# final_schematic.net
KiCad netlist of a schematic drawn in EAGLE
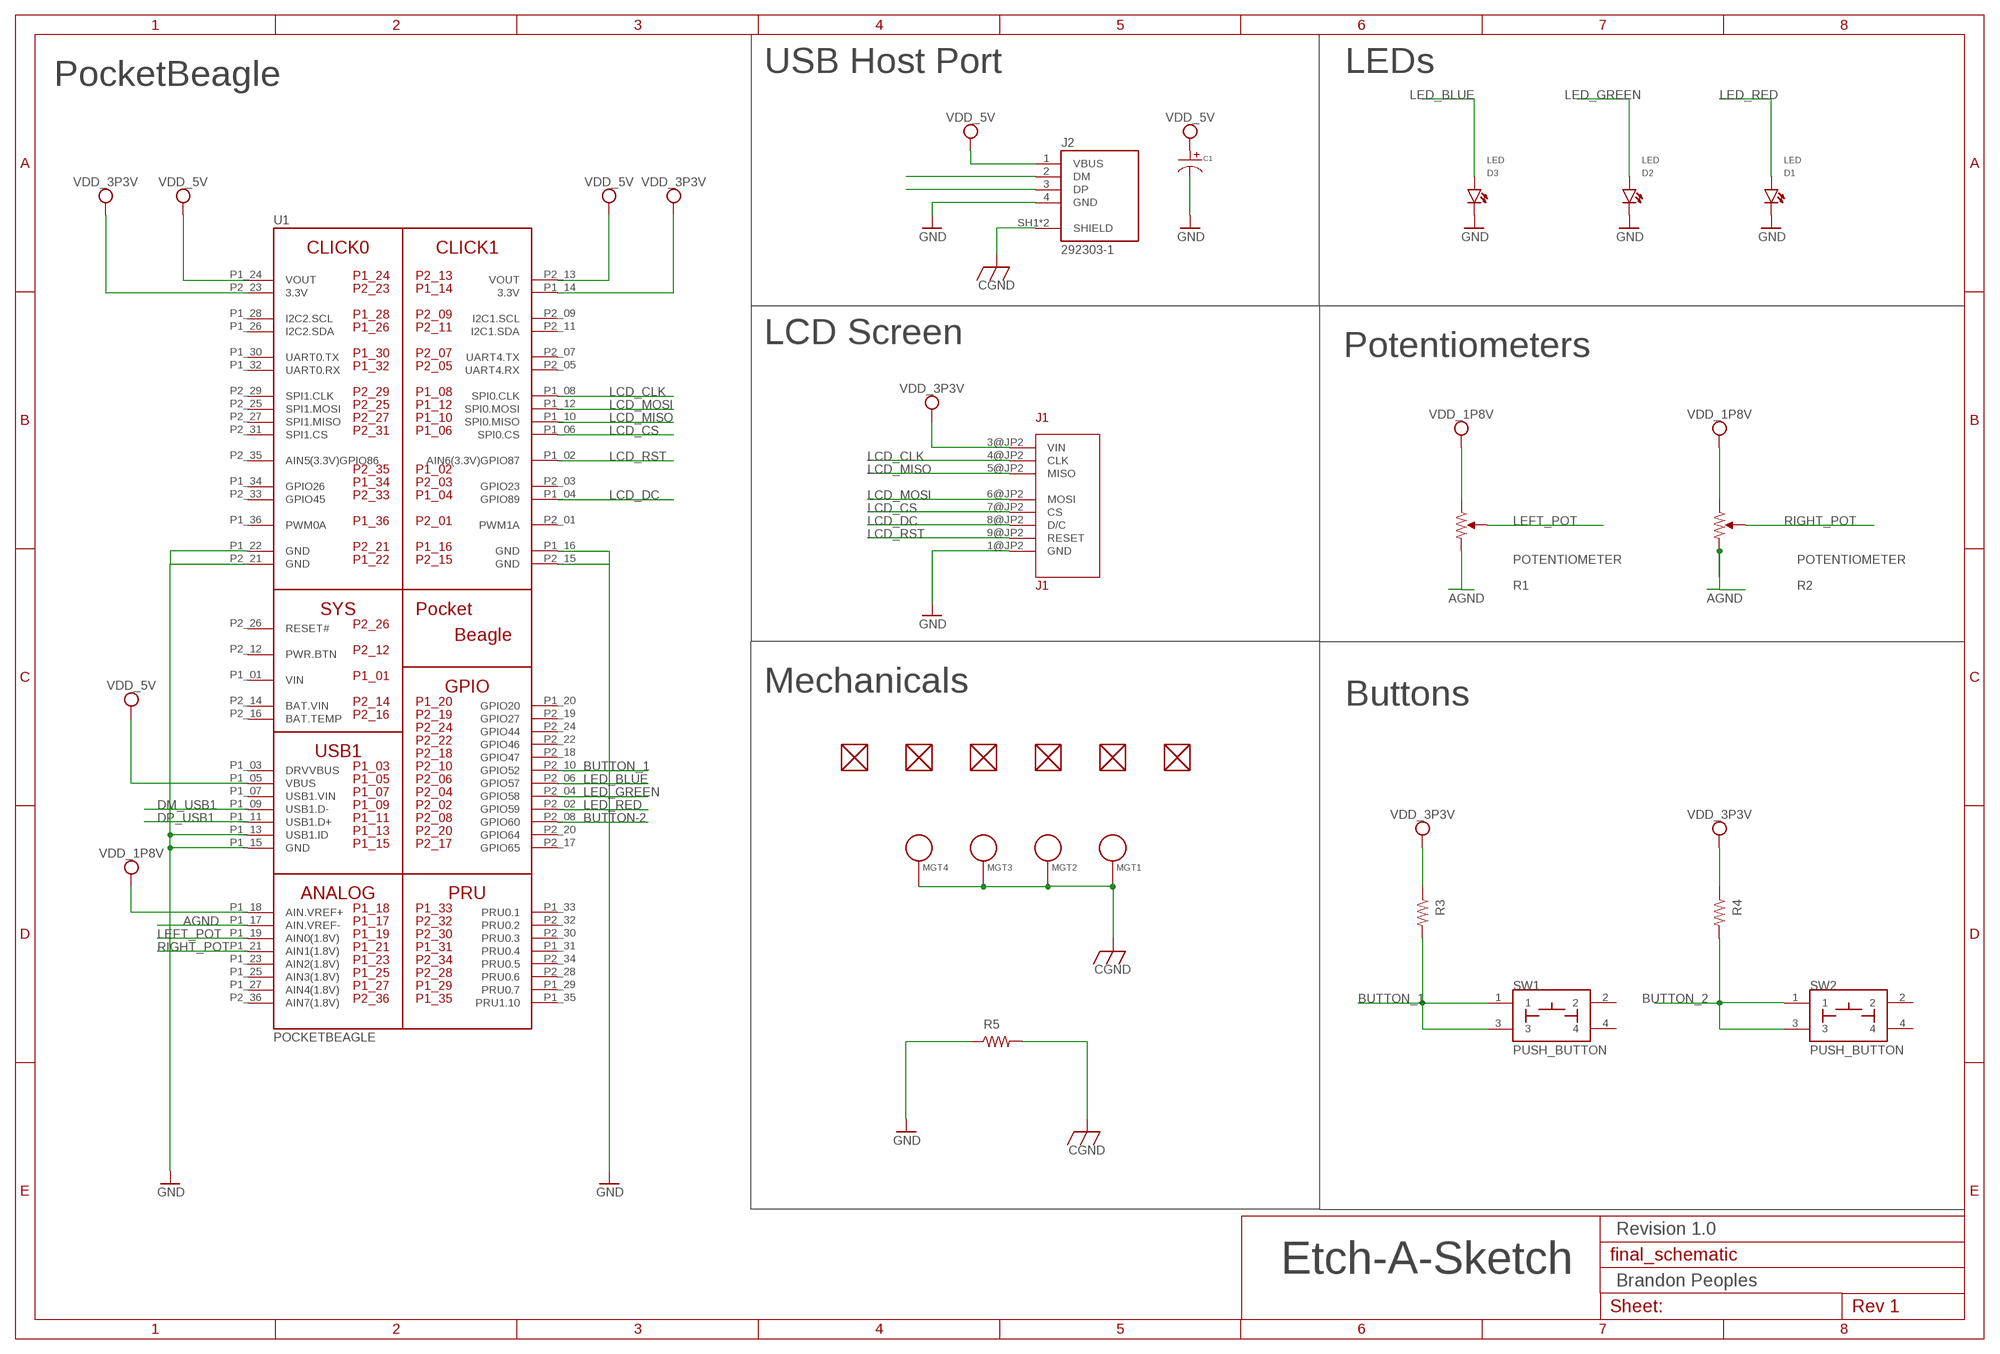
[diagram p0: schematic, sheet 1]

(export (version "E")
  (design (tool "Eeschema 10.0.6"))
  (components
    (comp (ref "C1")
      (value "CAPACITOR_P_10MM")
      (footprint "eagle-import:CP10MM")
      (libsource (lib "eagle-import") (part "CAPACITOR_P_10MM"))
    )
    (comp (ref "D1")
      (value "LED")
      (footprint "eagle-import:EIA-STD")
      (libsource (lib "eagle-import") (part "LED"))
    )
    (comp (ref "D2")
      (value "LED")
      (footprint "eagle-import:EIA-STD")
      (libsource (lib "eagle-import") (part "LED"))
    )
    (comp (ref "D3")
      (value "LED")
      (footprint "eagle-import:EIA-STD")
      (libsource (lib "eagle-import") (part "LED"))
    )
    (comp (ref "FUD1")
      (value "FIDUCIAL")
      (footprint "eagle-import:FIDUCIAL_40MIL")
      (libsource (lib "eagle-import") (part "FIDUCIAL"))
    )
    (comp (ref "FUD2")
      (value "FIDUCIAL")
      (footprint "eagle-import:FIDUCIAL_40MIL")
      (libsource (lib "eagle-import") (part "FIDUCIAL"))
    )
    (comp (ref "FUD4")
      (value "FIDUCIAL")
      (footprint "eagle-import:FIDUCIAL_40MIL")
      (libsource (lib "eagle-import") (part "FIDUCIAL"))
    )
    (comp (ref "FUD5")
      (value "FIDUCIAL")
      (footprint "eagle-import:FIDUCIAL_40MIL")
      (libsource (lib "eagle-import") (part "FIDUCIAL"))
    )
    (comp (ref "FUD6")
      (value "FIDUCIAL")
      (footprint "eagle-import:FIDUCIAL_40MIL")
      (libsource (lib "eagle-import") (part "FIDUCIAL"))
    )
    (comp (ref "FUD7")
      (value "FIDUCIAL")
      (footprint "eagle-import:FIDUCIAL_40MIL")
      (libsource (lib "eagle-import") (part "FIDUCIAL"))
    )
    (comp (ref "J1")
      (value "LCD")
      (footprint "eagle-import:TFT_LCD_PCB")
      (libsource (lib "eagle-import") (part "LCD"))
    )
    (comp (ref "J2")
      (value "292303-1")
      (footprint "eagle-import:TE_292303-1")
      (fields (field (name "MF") "TE Connectivity"))
      (libsource (lib "eagle-import") (part "292303-1"))
    )
    (comp (ref "MGT1")
      (value "MOUNTING_HOLE")
      (footprint "eagle-import:MOUNTING_HOLE")
      (libsource (lib "eagle-import") (part "MOUNTING_HOLE"))
    )
    (comp (ref "MGT2")
      (value "MOUNTING_HOLE")
      (footprint "eagle-import:MOUNTING_HOLE")
      (libsource (lib "eagle-import") (part "MOUNTING_HOLE"))
    )
    (comp (ref "MGT3")
      (value "MOUNTING_HOLE")
      (footprint "eagle-import:MOUNTING_HOLE")
      (libsource (lib "eagle-import") (part "MOUNTING_HOLE"))
    )
    (comp (ref "MGT4")
      (value "MOUNTING_HOLE")
      (footprint "eagle-import:MOUNTING_HOLE")
      (libsource (lib "eagle-import") (part "MOUNTING_HOLE"))
    )
    (comp (ref "R1")
      (value "POTENTIOMETER")
      (footprint "eagle-import:POT-PO90S")
      (libsource (lib "eagle-import") (part "POTENTIOMETER"))
    )
    (comp (ref "R2")
      (value "POTENTIOMETER")
      (footprint "eagle-import:POT-PO90S")
      (libsource (lib "eagle-import") (part "POTENTIOMETER"))
    )
    (comp (ref "R3")
      (value "R_R0402")
      (footprint "eagle-import:R0402")
      (libsource (lib "eagle-import") (part "R_R0402"))
    )
    (comp (ref "R4")
      (value "R_R0402")
      (footprint "eagle-import:R0402")
      (libsource (lib "eagle-import") (part "R_R0402"))
    )
    (comp (ref "R5")
      (value "R_R0402")
      (footprint "eagle-import:R0402")
      (libsource (lib "eagle-import") (part "R_R0402"))
    )
    (comp (ref "SW1")
      (value "PUSH_BUTTON")
      (footprint "eagle-import:BUTTON_12.5MM")
      (libsource (lib "eagle-import") (part "PUSH_BUTTON"))
    )
    (comp (ref "SW2")
      (value "PUSH_BUTTON")
      (footprint "eagle-import:BUTTON_12.5MM")
      (libsource (lib "eagle-import") (part "PUSH_BUTTON"))
    )
    (comp (ref "U1")
      (value "POCKETBEAGLE")
      (footprint "eagle-import:POCKETBEAGLE")
      (libsource (lib "eagle-import") (part "POCKETBEAGLE"))
    )
  )
  (nets
    (net (code "1") (name "/AGND") (class "Default")
      (node (ref "R1") (pin "CW") (pinfunction "CW_CW") (pintype "passive"))
      (node (ref "R2") (pin "CW") (pinfunction "CW_CW") (pintype "passive"))
      (node (ref "U1") (pin "P1_17") (pinfunction "AIN.VREF-_P1_17") (pintype "input"))
    )
    (net (code "2") (name "/BAT.VIN") (class "Default")
      (node (ref "U1") (pin "P2_14") (pinfunction "BAT.VIN_P2_14") (pintype "power_in"))
    )
    (net (code "3") (name "/BUTTON-2") (class "Default")
      (node (ref "U1") (pin "P2_08") (pinfunction "GPIO60_P2_08") (pintype "bidirectional"))
    )
    (net (code "4") (name "/BUTTON_1") (class "Default")
      (node (ref "R3") (pin "2") (pinfunction "2_2") (pintype "passive"))
      (node (ref "SW1") (pin "1") (pinfunction "1_1") (pintype "bidirectional"))
      (node (ref "SW1") (pin "3") (pinfunction "3_3") (pintype "bidirectional"))
      (node (ref "U1") (pin "P2_10") (pinfunction "GPIO52_P2_10") (pintype "bidirectional"))
    )
    (net (code "5") (name "/BUTTON_2") (class "Default")
      (node (ref "R4") (pin "2") (pinfunction "2_2") (pintype "passive"))
      (node (ref "SW2") (pin "1") (pinfunction "1_1") (pintype "bidirectional"))
      (node (ref "SW2") (pin "3") (pinfunction "3_3") (pintype "bidirectional"))
    )
    (net (code "6") (name "/LCD_CLK") (class "Default")
      (node (ref "J1") (pin "4@JP2") (pinfunction "CLK_4@JP2") (pintype "bidirectional"))
      (node (ref "U1") (pin "P1_08") (pinfunction "SPI0.CLK_P1_08") (pintype "bidirectional"))
    )
    (net (code "7") (name "/LCD_CS") (class "Default")
      (node (ref "J1") (pin "7@JP2") (pinfunction "CS_7@JP2") (pintype "bidirectional"))
      (node (ref "U1") (pin "P1_06") (pinfunction "SPI0.CS_P1_06") (pintype "bidirectional"))
    )
    (net (code "8") (name "/LCD_DC") (class "Default")
      (node (ref "J1") (pin "8@JP2") (pinfunction "D/C_8@JP2") (pintype "bidirectional"))
      (node (ref "U1") (pin "P1_04") (pinfunction "GPIO89_P1_04") (pintype "bidirectional"))
    )
    (net (code "9") (name "/LCD_MISO") (class "Default")
      (node (ref "J1") (pin "5@JP2") (pinfunction "MISO_5@JP2") (pintype "bidirectional"))
      (node (ref "U1") (pin "P1_10") (pinfunction "SPI0.MISO_P1_10") (pintype "bidirectional"))
    )
    (net (code "10") (name "/LCD_MOSI") (class "Default")
      (node (ref "J1") (pin "6@JP2") (pinfunction "MOSI_6@JP2") (pintype "bidirectional"))
      (node (ref "U1") (pin "P1_12") (pinfunction "SPI0.MOSI_P1_12") (pintype "bidirectional"))
    )
    (net (code "11") (name "/LCD_RST") (class "Default")
      (node (ref "J1") (pin "9@JP2") (pinfunction "RESET_9@JP2") (pintype "bidirectional"))
      (node (ref "U1") (pin "P1_02") (pinfunction "AIN6(3.3V)GPIO87_P1_02") (pintype "bidirectional"))
    )
    (net (code "12") (name "/LED_BLUE") (class "Default")
      (node (ref "D3") (pin "ANODE") (pinfunction "ANODE_ANODE") (pintype "bidirectional"))
      (node (ref "U1") (pin "P2_06") (pinfunction "GPIO57_P2_06") (pintype "bidirectional"))
    )
    (net (code "13") (name "/LED_GREEN") (class "Default")
      (node (ref "D2") (pin "ANODE") (pinfunction "ANODE_ANODE") (pintype "bidirectional"))
      (node (ref "U1") (pin "P2_04") (pinfunction "GPIO58_P2_04") (pintype "bidirectional"))
    )
    (net (code "14") (name "/LED_RED") (class "Default")
      (node (ref "D1") (pin "ANODE") (pinfunction "ANODE_ANODE") (pintype "bidirectional"))
      (node (ref "U1") (pin "P2_02") (pinfunction "GPIO59_P2_02") (pintype "bidirectional"))
    )
    (net (code "15") (name "/LEFT_POT") (class "Default")
      (node (ref "R1") (pin "S") (pinfunction "S_S") (pintype "bidirectional"))
      (node (ref "U1") (pin "P1_19") (pinfunction "AIN0(1.8V)_P1_19") (pintype "input"))
    )
    (net (code "16") (name "/RIGHT_POT") (class "Default")
      (node (ref "R2") (pin "S") (pinfunction "S_S") (pintype "bidirectional"))
      (node (ref "U1") (pin "P1_21") (pinfunction "AIN1(1.8V)_P1_21") (pintype "input"))
    )
    (net (code "17") (name "/VIN") (class "Default")
      (node (ref "U1") (pin "P1_01") (pinfunction "VIN_P1_01") (pintype "power_in"))
    )
    (net (code "18") (name "CGND") (class "Default")
      (node (ref "J2") (pin "SH1") (pinfunction "SHIELD_SH1") (pintype "passive"))
      (node (ref "J2") (pin "SH2") (pinfunction "SHIELD_SH2") (pintype "passive"))
      (node (ref "MGT1") (pin "P$1") (pinfunction "P$1_P$1") (pintype "bidirectional"))
      (node (ref "MGT2") (pin "P$1") (pinfunction "P$1_P$1") (pintype "bidirectional"))
      (node (ref "MGT3") (pin "P$1") (pinfunction "P$1_P$1") (pintype "bidirectional"))
      (node (ref "MGT4") (pin "P$1") (pinfunction "P$1_P$1") (pintype "bidirectional"))
      (node (ref "R5") (pin "2") (pinfunction "2_2") (pintype "passive"))
    )
    (net (code "19") (name "GND") (class "Default")
      (node (ref "C1") (pin "P$2") (pinfunction "P$2_P$2") (pintype "passive"))
      (node (ref "D1") (pin "CATHODE") (pinfunction "CATHODE_CATHODE") (pintype "bidirectional"))
      (node (ref "D2") (pin "CATHODE") (pinfunction "CATHODE_CATHODE") (pintype "bidirectional"))
      (node (ref "D3") (pin "CATHODE") (pinfunction "CATHODE_CATHODE") (pintype "bidirectional"))
      (node (ref "J1") (pin "1@JP2") (pinfunction "GND_1@JP2") (pintype "bidirectional"))
      (node (ref "J2") (pin "4") (pinfunction "GND_4") (pintype "passive"))
      (node (ref "R5") (pin "1") (pinfunction "1_1") (pintype "passive"))
      (node (ref "U1") (pin "P1_13") (pinfunction "USB1.ID_P1_13") (pintype "bidirectional"))
      (node (ref "U1") (pin "P1_15") (pinfunction "GND_P1_15") (pintype "bidirectional"))
      (node (ref "U1") (pin "P1_16") (pinfunction "GND_P1_16") (pintype "power_in"))
      (node (ref "U1") (pin "P1_22") (pinfunction "GND_P1_22") (pintype "power_in"))
      (node (ref "U1") (pin "P2_15") (pinfunction "GND_P2_15") (pintype "power_in"))
      (node (ref "U1") (pin "P2_21") (pinfunction "GND_P2_21") (pintype "power_in"))
    )
    (net (code "20") (name "VDD_1P8V") (class "Default")
      (node (ref "R1") (pin "CCW") (pinfunction "CCW_CCW") (pintype "passive"))
      (node (ref "R2") (pin "CCW") (pinfunction "CCW_CCW") (pintype "passive"))
      (node (ref "U1") (pin "P1_18") (pinfunction "AIN.VREF+_P1_18") (pintype "input"))
    )
    (net (code "21") (name "VDD_3P3V") (class "Default")
      (node (ref "J1") (pin "3@JP2") (pinfunction "VIN_3@JP2") (pintype "bidirectional"))
      (node (ref "R3") (pin "1") (pinfunction "1_1") (pintype "passive"))
      (node (ref "R4") (pin "1") (pinfunction "1_1") (pintype "passive"))
      (node (ref "U1") (pin "P1_14") (pinfunction "3.3V_P1_14") (pintype "power_in"))
      (node (ref "U1") (pin "P2_23") (pinfunction "3.3V_P2_23") (pintype "power_in"))
    )
    (net (code "22") (name "VDD_5V") (class "Default")
      (node (ref "C1") (pin "P$1") (pinfunction "P$1_P$1") (pintype "passive"))
      (node (ref "J2") (pin "1") (pinfunction "VBUS_1") (pintype "passive"))
      (node (ref "U1") (pin "P1_05") (pinfunction "VBUS_P1_05") (pintype "bidirectional"))
      (node (ref "U1") (pin "P1_24") (pinfunction "VOUT_P1_24") (pintype "power_in"))
      (node (ref "U1") (pin "P2_13") (pinfunction "VOUT_P2_13") (pintype "power_in"))
    )
    (net (code "23") (name "unconnected-(FUD1-PadP$1)") (class "Default")
      (node (ref "FUD1") (pin "P$1") (pinfunction "P$1_P$1") (pintype "no_connect"))
    )
    (net (code "24") (name "unconnected-(FUD2-PadP$1)") (class "Default")
      (node (ref "FUD2") (pin "P$1") (pinfunction "P$1_P$1") (pintype "no_connect"))
    )
    (net (code "25") (name "unconnected-(FUD4-PadP$1)") (class "Default")
      (node (ref "FUD4") (pin "P$1") (pinfunction "P$1_P$1") (pintype "no_connect"))
    )
    (net (code "26") (name "unconnected-(FUD5-PadP$1)") (class "Default")
      (node (ref "FUD5") (pin "P$1") (pinfunction "P$1_P$1") (pintype "no_connect"))
    )
    (net (code "27") (name "unconnected-(FUD6-PadP$1)") (class "Default")
      (node (ref "FUD6") (pin "P$1") (pinfunction "P$1_P$1") (pintype "no_connect"))
    )
    (net (code "28") (name "unconnected-(FUD7-PadP$1)") (class "Default")
      (node (ref "FUD7") (pin "P$1") (pinfunction "P$1_P$1") (pintype "no_connect"))
    )
    (net (code "29") (name "unconnected-(J2-DM-Pad2)") (class "Default")
      (node (ref "J2") (pin "2") (pinfunction "DM_2") (pintype "passive"))
    )
    (net (code "30") (name "unconnected-(J2-DP-Pad3)") (class "Default")
      (node (ref "J2") (pin "3") (pinfunction "DP_3") (pintype "passive"))
    )
    (net (code "31") (name "unconnected-(SW1-Pad2)") (class "Default")
      (node (ref "SW1") (pin "2") (pinfunction "2_2") (pintype "bidirectional"))
    )
    (net (code "32") (name "unconnected-(SW1-Pad4)") (class "Default")
      (node (ref "SW1") (pin "4") (pinfunction "4_4") (pintype "bidirectional"))
    )
    (net (code "33") (name "unconnected-(SW2-Pad2)") (class "Default")
      (node (ref "SW2") (pin "2") (pinfunction "2_2") (pintype "bidirectional"))
    )
    (net (code "34") (name "unconnected-(SW2-Pad4)") (class "Default")
      (node (ref "SW2") (pin "4") (pinfunction "4_4") (pintype "bidirectional"))
    )
    (net (code "35") (name "unconnected-(U1-AIN2(1.8V)-PadP1_23)") (class "Default")
      (node (ref "U1") (pin "P1_23") (pinfunction "AIN2(1.8V)_P1_23") (pintype "input"))
    )
    (net (code "36") (name "unconnected-(U1-AIN3(1.8V)-PadP1_25)") (class "Default")
      (node (ref "U1") (pin "P1_25") (pinfunction "AIN3(1.8V)_P1_25") (pintype "input"))
    )
    (net (code "37") (name "unconnected-(U1-AIN4(1.8V)-PadP1_27)") (class "Default")
      (node (ref "U1") (pin "P1_27") (pinfunction "AIN4(1.8V)_P1_27") (pintype "input"))
    )
    (net (code "38") (name "unconnected-(U1-AIN5(3.3V)GPIO86-PadP2_35)") (class "Default")
      (node (ref "U1") (pin "P2_35") (pinfunction "AIN5(3.3V)GPIO86_P2_35") (pintype "bidirectional"))
    )
    (net (code "39") (name "unconnected-(U1-AIN7(1.8V)-PadP2_36)") (class "Default")
      (node (ref "U1") (pin "P2_36") (pinfunction "AIN7(1.8V)_P2_36") (pintype "input"))
    )
    (net (code "40") (name "unconnected-(U1-BAT.TEMP-PadP2_16)") (class "Default")
      (node (ref "U1") (pin "P2_16") (pinfunction "BAT.TEMP_P2_16") (pintype "input"))
    )
    (net (code "41") (name "unconnected-(U1-DRVVBUS-PadP1_03)") (class "Default")
      (node (ref "U1") (pin "P1_03") (pinfunction "DRVVBUS_P1_03") (pintype "bidirectional"))
    )
    (net (code "42") (name "unconnected-(U1-GPIO20-PadP1_20)") (class "Default")
      (node (ref "U1") (pin "P1_20") (pinfunction "GPIO20_P1_20") (pintype "bidirectional"))
    )
    (net (code "43") (name "unconnected-(U1-GPIO23-PadP2_03)") (class "Default")
      (node (ref "U1") (pin "P2_03") (pinfunction "GPIO23_P2_03") (pintype "bidirectional"))
    )
    (net (code "44") (name "unconnected-(U1-GPIO26-PadP1_34)") (class "Default")
      (node (ref "U1") (pin "P1_34") (pinfunction "GPIO26_P1_34") (pintype "bidirectional"))
    )
    (net (code "45") (name "unconnected-(U1-GPIO27-PadP2_19)") (class "Default")
      (node (ref "U1") (pin "P2_19") (pinfunction "GPIO27_P2_19") (pintype "bidirectional"))
    )
    (net (code "46") (name "unconnected-(U1-GPIO44-PadP2_24)") (class "Default")
      (node (ref "U1") (pin "P2_24") (pinfunction "GPIO44_P2_24") (pintype "bidirectional"))
    )
    (net (code "47") (name "unconnected-(U1-GPIO45-PadP2_33)") (class "Default")
      (node (ref "U1") (pin "P2_33") (pinfunction "GPIO45_P2_33") (pintype "bidirectional"))
    )
    (net (code "48") (name "unconnected-(U1-GPIO46-PadP2_22)") (class "Default")
      (node (ref "U1") (pin "P2_22") (pinfunction "GPIO46_P2_22") (pintype "bidirectional"))
    )
    (net (code "49") (name "unconnected-(U1-GPIO47-PadP2_18)") (class "Default")
      (node (ref "U1") (pin "P2_18") (pinfunction "GPIO47_P2_18") (pintype "bidirectional"))
    )
    (net (code "50") (name "unconnected-(U1-GPIO64-PadP2_20)") (class "Default")
      (node (ref "U1") (pin "P2_20") (pinfunction "GPIO64_P2_20") (pintype "bidirectional"))
    )
    (net (code "51") (name "unconnected-(U1-GPIO65-PadP2_17)") (class "Default")
      (node (ref "U1") (pin "P2_17") (pinfunction "GPIO65_P2_17") (pintype "bidirectional"))
    )
    (net (code "52") (name "unconnected-(U1-I2C1.SCL-PadP2_09)") (class "Default")
      (node (ref "U1") (pin "P2_09") (pinfunction "I2C1.SCL_P2_09") (pintype "bidirectional"))
    )
    (net (code "53") (name "unconnected-(U1-I2C1.SDA-PadP2_11)") (class "Default")
      (node (ref "U1") (pin "P2_11") (pinfunction "I2C1.SDA_P2_11") (pintype "bidirectional"))
    )
    (net (code "54") (name "unconnected-(U1-I2C2.SCL-PadP1_28)") (class "Default")
      (node (ref "U1") (pin "P1_28") (pinfunction "I2C2.SCL_P1_28") (pintype "bidirectional"))
    )
    (net (code "55") (name "unconnected-(U1-I2C2.SDA-PadP1_26)") (class "Default")
      (node (ref "U1") (pin "P1_26") (pinfunction "I2C2.SDA_P1_26") (pintype "bidirectional"))
    )
    (net (code "56") (name "unconnected-(U1-PRU0.1-PadP1_33)") (class "Default")
      (node (ref "U1") (pin "P1_33") (pinfunction "PRU0.1_P1_33") (pintype "bidirectional"))
    )
    (net (code "57") (name "unconnected-(U1-PRU0.2-PadP2_32)") (class "Default")
      (node (ref "U1") (pin "P2_32") (pinfunction "PRU0.2_P2_32") (pintype "bidirectional"))
    )
    (net (code "58") (name "unconnected-(U1-PRU0.3-PadP2_30)") (class "Default")
      (node (ref "U1") (pin "P2_30") (pinfunction "PRU0.3_P2_30") (pintype "bidirectional"))
    )
    (net (code "59") (name "unconnected-(U1-PRU0.4-PadP1_31)") (class "Default")
      (node (ref "U1") (pin "P1_31") (pinfunction "PRU0.4_P1_31") (pintype "bidirectional"))
    )
    (net (code "60") (name "unconnected-(U1-PRU0.5-PadP2_34)") (class "Default")
      (node (ref "U1") (pin "P2_34") (pinfunction "PRU0.5_P2_34") (pintype "bidirectional"))
    )
    (net (code "61") (name "unconnected-(U1-PRU0.6-PadP2_28)") (class "Default")
      (node (ref "U1") (pin "P2_28") (pinfunction "PRU0.6_P2_28") (pintype "bidirectional"))
    )
    (net (code "62") (name "unconnected-(U1-PRU0.7-PadP1_29)") (class "Default")
      (node (ref "U1") (pin "P1_29") (pinfunction "PRU0.7_P1_29") (pintype "bidirectional"))
    )
    (net (code "63") (name "unconnected-(U1-PRU1.10-PadP1_35)") (class "Default")
      (node (ref "U1") (pin "P1_35") (pinfunction "PRU1.10_P1_35") (pintype "bidirectional"))
    )
    (net (code "64") (name "unconnected-(U1-PWM0A-PadP1_36)") (class "Default")
      (node (ref "U1") (pin "P1_36") (pinfunction "PWM0A_P1_36") (pintype "bidirectional"))
    )
    (net (code "65") (name "unconnected-(U1-PWM1A-PadP2_01)") (class "Default")
      (node (ref "U1") (pin "P2_01") (pinfunction "PWM1A_P2_01") (pintype "bidirectional"))
    )
    (net (code "66") (name "unconnected-(U1-PWR.BTN-PadP2_12)") (class "Default")
      (node (ref "U1") (pin "P2_12") (pinfunction "PWR.BTN_P2_12") (pintype "input"))
    )
    (net (code "67") (name "unconnected-(U1-RESET#-PadP2_26)") (class "Default")
      (node (ref "U1") (pin "P2_26") (pinfunction "RESET#_P2_26") (pintype "input"))
    )
    (net (code "68") (name "unconnected-(U1-SPI1.CLK-PadP2_29)") (class "Default")
      (node (ref "U1") (pin "P2_29") (pinfunction "SPI1.CLK_P2_29") (pintype "bidirectional"))
    )
    (net (code "69") (name "unconnected-(U1-SPI1.CS-PadP2_31)") (class "Default")
      (node (ref "U1") (pin "P2_31") (pinfunction "SPI1.CS_P2_31") (pintype "bidirectional"))
    )
    (net (code "70") (name "unconnected-(U1-SPI1.MISO-PadP2_27)") (class "Default")
      (node (ref "U1") (pin "P2_27") (pinfunction "SPI1.MISO_P2_27") (pintype "bidirectional"))
    )
    (net (code "71") (name "unconnected-(U1-SPI1.MOSI-PadP2_25)") (class "Default")
      (node (ref "U1") (pin "P2_25") (pinfunction "SPI1.MOSI_P2_25") (pintype "bidirectional"))
    )
    (net (code "72") (name "unconnected-(U1-UART0.RX-PadP1_32)") (class "Default")
      (node (ref "U1") (pin "P1_32") (pinfunction "UART0.RX_P1_32") (pintype "bidirectional"))
    )
    (net (code "73") (name "unconnected-(U1-UART0.TX-PadP1_30)") (class "Default")
      (node (ref "U1") (pin "P1_30") (pinfunction "UART0.TX_P1_30") (pintype "bidirectional"))
    )
    (net (code "74") (name "unconnected-(U1-UART4.RX-PadP2_05)") (class "Default")
      (node (ref "U1") (pin "P2_05") (pinfunction "UART4.RX_P2_05") (pintype "bidirectional"))
    )
    (net (code "75") (name "unconnected-(U1-UART4.TX-PadP2_07)") (class "Default")
      (node (ref "U1") (pin "P2_07") (pinfunction "UART4.TX_P2_07") (pintype "bidirectional"))
    )
    (net (code "76") (name "unconnected-(U1-USB1.D+-PadP1_11)") (class "Default")
      (node (ref "U1") (pin "P1_11") (pinfunction "USB1.D+_P1_11") (pintype "bidirectional"))
    )
    (net (code "77") (name "unconnected-(U1-USB1.D--PadP1_09)") (class "Default")
      (node (ref "U1") (pin "P1_09") (pinfunction "USB1.D-_P1_09") (pintype "bidirectional"))
    )
    (net (code "78") (name "unconnected-(U1-USB1.VIN-PadP1_07)") (class "Default")
      (node (ref "U1") (pin "P1_07") (pinfunction "USB1.VIN_P1_07") (pintype "bidirectional"))
    )
  )
)
